# FFB_Arduino_Yoke_2_0_ProMicro.net
KiCad netlist of a schematic drawn in EasyEDA
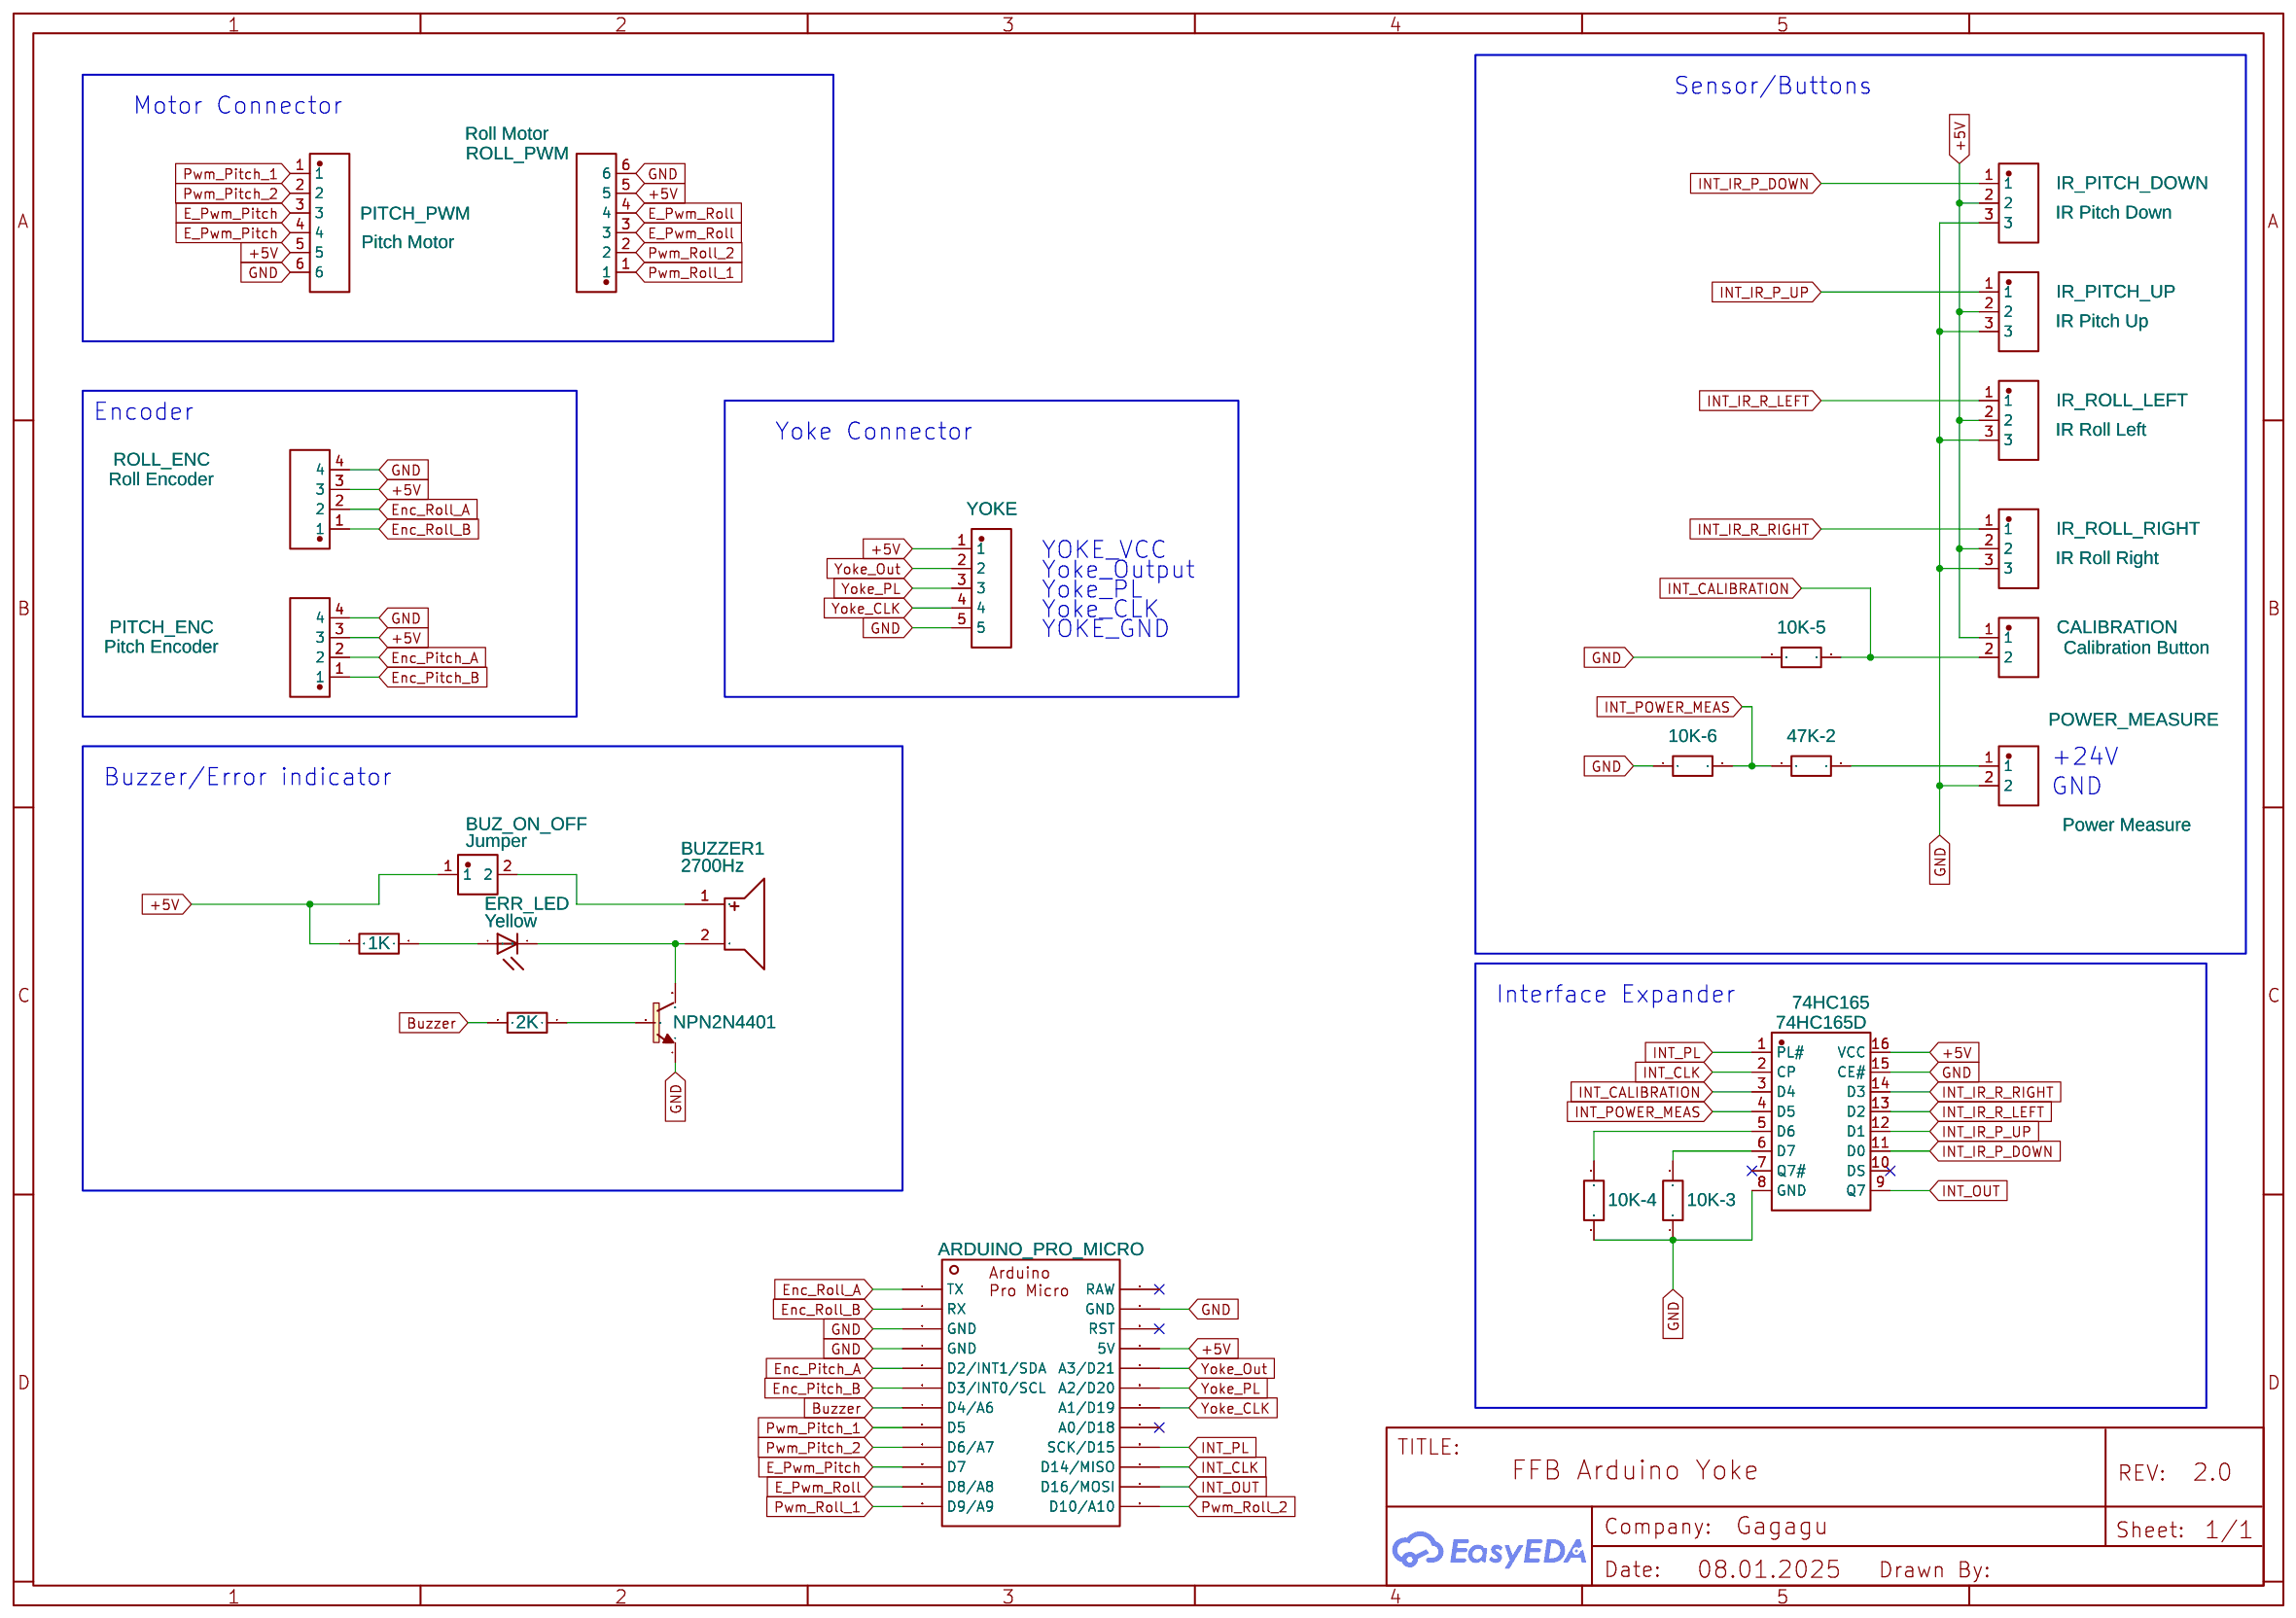
[diagram p0: schematic sheet]

(export (version "E")
  (design (tool "Eeschema 10.0.6"))
  (components
    (comp (ref "1K") (value "10k") (libsource (lib "") (part "R_AXIAL-0.3_EU_3")))
    (comp (ref "2K") (value "10k") (libsource (lib "") (part "R_AXIAL-0.3_EU")))
    (comp (ref "2N4401") (value "NPN2N4401") (libsource (lib "") (part "NPN2N4401")))
    (comp (ref "10K-3") (value "10k") (libsource (lib "") (part "R_AXIAL-0.3_EU_4")))
    (comp (ref "10K-4") (value "10k") (libsource (lib "") (part "R_AXIAL-0.3_EU_4")))
    (comp (ref "10K-5") (value "10k") (libsource (lib "") (part "R_AXIAL-0.3_EU_2")))
    (comp (ref "10K-6") (value "10k") (libsource (lib "") (part "R_AXIAL-0.3_EU_2")))
    (comp (ref "47K-2") (value "47k") (libsource (lib "") (part "R_AXIAL-0.3_EU_1")))
    (comp (ref "74HC165")
      (value "74HC165D")
      (fields
        (field (name "Manufacturer Part") "AiP74HC165DA.TB")
        (field (name "Manufacturer") "I-CORE(中微爱芯)")
      )
      (libsource (lib "") (part "AIP74HC165DA.TB"))
    )
    (comp (ref "ARDUINO_PRO_MICRO")
      (value "ArduinoProMicro")
      (libsource (lib "") (part "ArduinoProMicro_Ra"))
    )
    (comp (ref "BUZZER1")
      (value "2700Hz")
      (fields (field (name "Manufacturer Part") "QMB-09B-03") (field (name "Manufacturer") "华能"))
      (libsource (lib "") (part "QMB-09B-03"))
    )
    (comp (ref "BUZ_ON_OFF")
      (value "Jumper")
      (fields (field (name "Manufacturer Part") "XG8T-0231") (field (name "Manufacturer") "OMRON(欧姆龙)"))
      (libsource (lib "") (part "XG8T-0231"))
    )
    (comp (ref "CALIBRATION")
      (value "Calibration Button")
      (fields
        (field (name "Manufacturer Part") "MX128-2.54-02P-GN01-Cu-Y-A")
        (field (name "Manufacturer") "MAX(迈旭)")
      )
      (libsource (lib "") (part "MX128-2.54-02P-GN01-CU-Y-A"))
    )
    (comp (ref "ERR_LED") (value "Yellow") (libsource (lib "") (part "LED 3MM COPY")))
    (comp (ref "IR_PITCH_DOWN")
      (value "IR Pitch Down")
      (fields
        (field (name "Manufacturer Part") "MX128-2.54-03P-GN01-Cu-Y-A")
        (field (name "Manufacturer") "MAX(迈旭)")
      )
      (libsource (lib "") (part "MX128-2.54-03P-GN01-CU-Y-A_3"))
    )
    (comp (ref "IR_PITCH_UP")
      (value "IR Pitch Up")
      (fields
        (field (name "Manufacturer Part") "MX128-2.54-03P-GN01-Cu-Y-A")
        (field (name "Manufacturer") "MAX(迈旭)")
      )
      (libsource (lib "") (part "MX128-2.54-03P-GN01-CU-Y-A_1"))
    )
    (comp (ref "IR_ROLL_LEFT")
      (value "IR Roll Left")
      (fields
        (field (name "Manufacturer Part") "MX128-2.54-03P-GN01-Cu-Y-A")
        (field (name "Manufacturer") "MAX(迈旭)")
      )
      (libsource (lib "") (part "MX128-2.54-03P-GN01-CU-Y-A_2"))
    )
    (comp (ref "IR_ROLL_RIGHT")
      (value "IR Roll Right")
      (fields
        (field (name "Manufacturer Part") "MX128-2.54-03P-GN01-Cu-Y-A")
        (field (name "Manufacturer") "MAX(迈旭)")
      )
      (libsource (lib "") (part "MX128-2.54-03P-GN01-CU-Y-A"))
    )
    (comp (ref "PITCH_ENC")
      (value "Pitch Encoder")
      (fields
        (field (name "Manufacturer Part") "MX128-2.54-04P-GN01-Cu-Y-A")
        (field (name "Manufacturer") "MAX(迈旭)")
      )
      (libsource (lib "") (part "MX128-2.54-04P-GN01-CU-Y-A_1"))
    )
    (comp (ref "PITCH_PWM")
      (value "Pitch Motor")
      (fields
        (field (name "Manufacturer Part") "MX128-2.54-GN01-06P-Cu-Y-A")
        (field (name "Manufacturer") "MAX(迈旭)")
      )
      (libsource (lib "") (part "MX128-2.54-GN01-06P-CU-Y-A_1"))
    )
    (comp (ref "POWER_MEASURE")
      (value "Power Measure")
      (fields
        (field (name "Manufacturer Part") "MX128-2.54-02P-GN01-Cu-Y-A")
        (field (name "Manufacturer") "MAX(迈旭)")
      )
      (libsource (lib "") (part "MX128-2.54-02P-GN01-CU-Y-A_1"))
    )
    (comp (ref "ROLL_ENC")
      (value "Roll Encoder")
      (fields
        (field (name "Manufacturer Part") "MX128-2.54-04P-GN01-Cu-Y-A")
        (field (name "Manufacturer") "MAX(迈旭)")
      )
      (libsource (lib "") (part "MX128-2.54-04P-GN01-CU-Y-A"))
    )
    (comp (ref "ROLL_PWM")
      (value "Roll Motor")
      (fields
        (field (name "Manufacturer Part") "MX128-2.54-GN01-06P-Cu-Y-A")
        (field (name "Manufacturer") "MAX(迈旭)")
      )
      (libsource (lib "") (part "MX128-2.54-GN01-06P-CU-Y-A"))
    )
    (comp (ref "YOKE")
      (value "Yoke")
      (fields
        (field (name "Manufacturer Part") "MX128-2.54-05P-GN01-Cu-Y-A")
        (field (name "Manufacturer") "MAX(迈旭)")
      )
      (libsource (lib "") (part "MX128-2.54-05P-GN01-CU-Y-A"))
    )
  )
  (nets
    (net (code "1") (name "+5V") (class "Default")
      (node (ref "1K") (pin "2") (pinfunction "2_2") (pintype "unspecified"))
      (node (ref "74HC165") (pin "16") (pinfunction "VCC_16") (pintype "unspecified"))
      (node (ref "ARDUINO_PRO_MICRO") (pin "21") (pinfunction "5V_21") (pintype "unspecified"))
      (node (ref "BUZ_ON_OFF") (pin "1") (pinfunction "1_1") (pintype "unspecified"))
      (node (ref "CALIBRATION") (pin "1") (pinfunction "1_1") (pintype "unspecified"))
      (node (ref "IR_PITCH_DOWN") (pin "2") (pinfunction "2_2") (pintype "unspecified"))
      (node (ref "IR_PITCH_UP") (pin "2") (pinfunction "2_2") (pintype "unspecified"))
      (node (ref "IR_ROLL_LEFT") (pin "2") (pinfunction "2_2") (pintype "unspecified"))
      (node (ref "IR_ROLL_RIGHT") (pin "2") (pinfunction "2_2") (pintype "unspecified"))
      (node (ref "PITCH_ENC") (pin "3") (pinfunction "3_3") (pintype "unspecified"))
      (node (ref "PITCH_PWM") (pin "5") (pinfunction "5_5") (pintype "unspecified"))
      (node (ref "ROLL_ENC") (pin "3") (pinfunction "3_3") (pintype "unspecified"))
      (node (ref "ROLL_PWM") (pin "5") (pinfunction "5_5") (pintype "unspecified"))
      (node (ref "YOKE") (pin "1") (pinfunction "1_1") (pintype "unspecified"))
    )
    (net (code "2") (name "Buzzer") (class "Default")
      (node (ref "2K") (pin "2") (pinfunction "2_2") (pintype "unspecified"))
      (node (ref "ARDUINO_PRO_MICRO") (pin "7") (pinfunction "D4/A6_7") (pintype "unspecified"))
    )
    (net (code "3") (name "E_Pwm_Pitch") (class "Default")
      (node (ref "ARDUINO_PRO_MICRO") (pin "10") (pinfunction "D7_10") (pintype "unspecified"))
      (node (ref "PITCH_PWM") (pin "3") (pinfunction "3_3") (pintype "unspecified"))
      (node (ref "PITCH_PWM") (pin "4") (pinfunction "4_4") (pintype "unspecified"))
    )
    (net (code "4") (name "E_Pwm_Roll") (class "Default")
      (node (ref "ARDUINO_PRO_MICRO") (pin "11") (pinfunction "D8/A8_11") (pintype "unspecified"))
      (node (ref "ROLL_PWM") (pin "3") (pinfunction "3_3") (pintype "unspecified"))
      (node (ref "ROLL_PWM") (pin "4") (pinfunction "4_4") (pintype "unspecified"))
    )
    (net (code "5") (name "Enc_Pitch_A") (class "Default")
      (node (ref "ARDUINO_PRO_MICRO") (pin "5") (pinfunction "D2/INT1/SDA_5") (pintype "unspecified"))
      (node (ref "PITCH_ENC") (pin "2") (pinfunction "2_2") (pintype "unspecified"))
    )
    (net (code "6") (name "Enc_Pitch_B") (class "Default")
      (node (ref "ARDUINO_PRO_MICRO") (pin "6") (pinfunction "D3/INT0/SCL_6") (pintype "unspecified"))
      (node (ref "PITCH_ENC") (pin "1") (pinfunction "1_1") (pintype "unspecified"))
    )
    (net (code "7") (name "Enc_Roll_A") (class "Default")
      (node (ref "ARDUINO_PRO_MICRO") (pin "1") (pinfunction "TX_1") (pintype "unspecified"))
      (node (ref "ROLL_ENC") (pin "2") (pinfunction "2_2") (pintype "unspecified"))
    )
    (net (code "8") (name "Enc_Roll_B") (class "Default")
      (node (ref "ARDUINO_PRO_MICRO") (pin "2") (pinfunction "RX_2") (pintype "unspecified"))
      (node (ref "ROLL_ENC") (pin "1") (pinfunction "1_1") (pintype "unspecified"))
    )
    (net (code "9") (name "GND") (class "Default")
      (node (ref "10K-3") (pin "1") (pinfunction "1_1") (pintype "unspecified"))
      (node (ref "10K-4") (pin "1") (pinfunction "1_1") (pintype "unspecified"))
      (node (ref "10K-5") (pin "1") (pinfunction "1_1") (pintype "unspecified"))
      (node (ref "10K-6") (pin "1") (pinfunction "1_1") (pintype "unspecified"))
      (node (ref "2N4401") (pin "E") (pinfunction "E_E") (pintype "bidirectional"))
      (node (ref "74HC165") (pin "15") (pinfunction "CE#_15") (pintype "unspecified"))
      (node (ref "74HC165") (pin "8") (pinfunction "GND_8") (pintype "unspecified"))
      (node (ref "ARDUINO_PRO_MICRO") (pin "23") (pinfunction "GND_23") (pintype "unspecified"))
      (node (ref "ARDUINO_PRO_MICRO") (pin "3") (pinfunction "GND_3") (pintype "unspecified"))
      (node (ref "ARDUINO_PRO_MICRO") (pin "4") (pinfunction "GND_4") (pintype "unspecified"))
      (node (ref "IR_PITCH_DOWN") (pin "3") (pinfunction "3_3") (pintype "unspecified"))
      (node (ref "IR_PITCH_UP") (pin "3") (pinfunction "3_3") (pintype "unspecified"))
      (node (ref "IR_ROLL_LEFT") (pin "3") (pinfunction "3_3") (pintype "unspecified"))
      (node (ref "IR_ROLL_RIGHT") (pin "3") (pinfunction "3_3") (pintype "unspecified"))
      (node (ref "PITCH_ENC") (pin "4") (pinfunction "4_4") (pintype "unspecified"))
      (node (ref "PITCH_PWM") (pin "6") (pinfunction "6_6") (pintype "unspecified"))
      (node (ref "POWER_MEASURE") (pin "2") (pinfunction "2_2") (pintype "unspecified"))
      (node (ref "ROLL_ENC") (pin "4") (pinfunction "4_4") (pintype "unspecified"))
      (node (ref "ROLL_PWM") (pin "6") (pinfunction "6_6") (pintype "unspecified"))
      (node (ref "YOKE") (pin "5") (pinfunction "5_5") (pintype "unspecified"))
    )
    (net (code "10") (name "INT_CALIBRATION") (class "Default")
      (node (ref "10K-5") (pin "2") (pinfunction "2_2") (pintype "unspecified"))
      (node (ref "74HC165") (pin "3") (pinfunction "D4_3") (pintype "unspecified"))
      (node (ref "CALIBRATION") (pin "2") (pinfunction "2_2") (pintype "unspecified"))
    )
    (net (code "11") (name "INT_CLK") (class "Default")
      (node (ref "74HC165") (pin "2") (pinfunction "CP_2") (pintype "unspecified"))
      (node (ref "ARDUINO_PRO_MICRO") (pin "15") (pinfunction "D14/MISO_15") (pintype "unspecified"))
    )
    (net (code "12") (name "INT_IR_P_DOWN") (class "Default")
      (node (ref "74HC165") (pin "11") (pinfunction "D0_11") (pintype "unspecified"))
      (node (ref "IR_PITCH_DOWN") (pin "1") (pinfunction "1_1") (pintype "unspecified"))
    )
    (net (code "13") (name "INT_IR_P_UP") (class "Default")
      (node (ref "74HC165") (pin "12") (pinfunction "D1_12") (pintype "unspecified"))
      (node (ref "IR_PITCH_UP") (pin "1") (pinfunction "1_1") (pintype "unspecified"))
    )
    (net (code "14") (name "INT_IR_R_LEFT") (class "Default")
      (node (ref "74HC165") (pin "13") (pinfunction "D2_13") (pintype "unspecified"))
      (node (ref "IR_ROLL_LEFT") (pin "1") (pinfunction "1_1") (pintype "unspecified"))
    )
    (net (code "15") (name "INT_IR_R_RIGHT") (class "Default")
      (node (ref "74HC165") (pin "14") (pinfunction "D3_14") (pintype "unspecified"))
      (node (ref "IR_ROLL_RIGHT") (pin "1") (pinfunction "1_1") (pintype "unspecified"))
    )
    (net (code "16") (name "INT_OUT") (class "Default")
      (node (ref "74HC165") (pin "9") (pinfunction "Q7_9") (pintype "unspecified"))
      (node (ref "ARDUINO_PRO_MICRO") (pin "14") (pinfunction "D16/MOSI_14") (pintype "unspecified"))
    )
    (net (code "17") (name "INT_PL") (class "Default")
      (node (ref "74HC165") (pin "1") (pinfunction "PL#_1") (pintype "unspecified"))
      (node (ref "ARDUINO_PRO_MICRO") (pin "16") (pinfunction "SCK/D15_16") (pintype "unspecified"))
    )
    (net (code "18") (name "INT_POWER_MEAS") (class "Default")
      (node (ref "10K-6") (pin "2") (pinfunction "2_2") (pintype "unspecified"))
      (node (ref "47K-2") (pin "1") (pinfunction "1_1") (pintype "unspecified"))
      (node (ref "74HC165") (pin "4") (pinfunction "D5_4") (pintype "unspecified"))
    )
    (net (code "19") (name "Net-(1K-Pad1)") (class "Default")
      (node (ref "1K") (pin "1") (pinfunction "1_1") (pintype "unspecified"))
      (node (ref "ERR_LED") (pin "A") (pinfunction "A_A") (pintype "unspecified"))
    )
    (net (code "20") (name "Net-(2K-Pad1)") (class "Default")
      (node (ref "2K") (pin "1") (pinfunction "1_1") (pintype "unspecified"))
      (node (ref "2N4401") (pin "B") (pinfunction "B_B") (pintype "bidirectional"))
    )
    (net (code "21") (name "Net-(47K-2-Pad2)") (class "Default")
      (node (ref "47K-2") (pin "2") (pinfunction "2_2") (pintype "unspecified"))
      (node (ref "POWER_MEASURE") (pin "1") (pinfunction "1_1") (pintype "unspecified"))
    )
    (net (code "22") (name "Net-(74HC165-D6)") (class "Default")
      (node (ref "10K-4") (pin "2") (pinfunction "2_2") (pintype "unspecified"))
      (node (ref "74HC165") (pin "5") (pinfunction "D6_5") (pintype "unspecified"))
    )
    (net (code "23") (name "Net-(74HC165-D7)") (class "Default")
      (node (ref "10K-3") (pin "2") (pinfunction "2_2") (pintype "unspecified"))
      (node (ref "74HC165") (pin "6") (pinfunction "D7_6") (pintype "unspecified"))
    )
    (net (code "24") (name "Net-(BUZZER1-Pad1)") (class "Default")
      (node (ref "BUZZER1") (pin "1") (pinfunction "1_1") (pintype "unspecified"))
      (node (ref "BUZ_ON_OFF") (pin "2") (pinfunction "2_2") (pintype "unspecified"))
    )
    (net (code "25") (name "Net-(ERR_LED-C)") (class "Default")
      (node (ref "2N4401") (pin "C") (pinfunction "C_C") (pintype "bidirectional"))
      (node (ref "BUZZER1") (pin "2") (pinfunction "2_2") (pintype "unspecified"))
      (node (ref "ERR_LED") (pin "K") (pinfunction "C_K") (pintype "unspecified"))
    )
    (net (code "26") (name "Pwm_Pitch_1") (class "Default")
      (node (ref "ARDUINO_PRO_MICRO") (pin "8") (pinfunction "D5_8") (pintype "unspecified"))
      (node (ref "PITCH_PWM") (pin "1") (pinfunction "1_1") (pintype "unspecified"))
    )
    (net (code "27") (name "Pwm_Pitch_2") (class "Default")
      (node (ref "ARDUINO_PRO_MICRO") (pin "9") (pinfunction "D6/A7_9") (pintype "unspecified"))
      (node (ref "PITCH_PWM") (pin "2") (pinfunction "2_2") (pintype "unspecified"))
    )
    (net (code "28") (name "Pwm_Roll_1") (class "Default")
      (node (ref "ARDUINO_PRO_MICRO") (pin "12") (pinfunction "D9/A9_12") (pintype "unspecified"))
      (node (ref "ROLL_PWM") (pin "1") (pinfunction "1_1") (pintype "unspecified"))
    )
    (net (code "29") (name "Pwm_Roll_2") (class "Default")
      (node (ref "ARDUINO_PRO_MICRO") (pin "13") (pinfunction "D10/A10_13") (pintype "unspecified"))
      (node (ref "ROLL_PWM") (pin "2") (pinfunction "2_2") (pintype "unspecified"))
    )
    (net (code "30") (name "Yoke_CLK") (class "Default")
      (node (ref "ARDUINO_PRO_MICRO") (pin "18") (pinfunction "A1/D19_18") (pintype "unspecified"))
      (node (ref "YOKE") (pin "4") (pinfunction "4_4") (pintype "unspecified"))
    )
    (net (code "31") (name "Yoke_Out") (class "Default")
      (node (ref "ARDUINO_PRO_MICRO") (pin "20") (pinfunction "A3/D21_20") (pintype "unspecified"))
      (node (ref "YOKE") (pin "2") (pinfunction "2_2") (pintype "unspecified"))
    )
    (net (code "32") (name "Yoke_PL") (class "Default")
      (node (ref "ARDUINO_PRO_MICRO") (pin "19") (pinfunction "A2/D20_19") (pintype "unspecified"))
      (node (ref "YOKE") (pin "3") (pinfunction "3_3") (pintype "unspecified"))
    )
    (net (code "33") (name "unconnected-(74HC165-DS-Pad10)") (class "Default")
      (node (ref "74HC165") (pin "10") (pinfunction "DS_10") (pintype "unspecified+no_connect"))
    )
    (net (code "34") (name "unconnected-(74HC165-Q7#-Pad7)") (class "Default")
      (node (ref "74HC165") (pin "7") (pinfunction "Q7#_7") (pintype "unspecified+no_connect"))
    )
    (net (code "35") (name "unconnected-(ARDUINO_PRO_MICRO-A0{slash}D18-Pad17)") (class "Default")
      (node (ref "ARDUINO_PRO_MICRO") (pin "17") (pinfunction "A0/D18_17") (pintype "unspecified+no_connect"))
    )
    (net (code "36") (name "unconnected-(ARDUINO_PRO_MICRO-RAW-Pad24)") (class "Default")
      (node (ref "ARDUINO_PRO_MICRO") (pin "24") (pinfunction "RAW_24") (pintype "unspecified+no_connect"))
    )
    (net (code "37") (name "unconnected-(ARDUINO_PRO_MICRO-RST-Pad22)") (class "Default")
      (node (ref "ARDUINO_PRO_MICRO") (pin "22") (pinfunction "RST_22") (pintype "unspecified+no_connect"))
    )
  )
)
